# its2.net
KiCad netlist of a schematic drawn in EAGLE
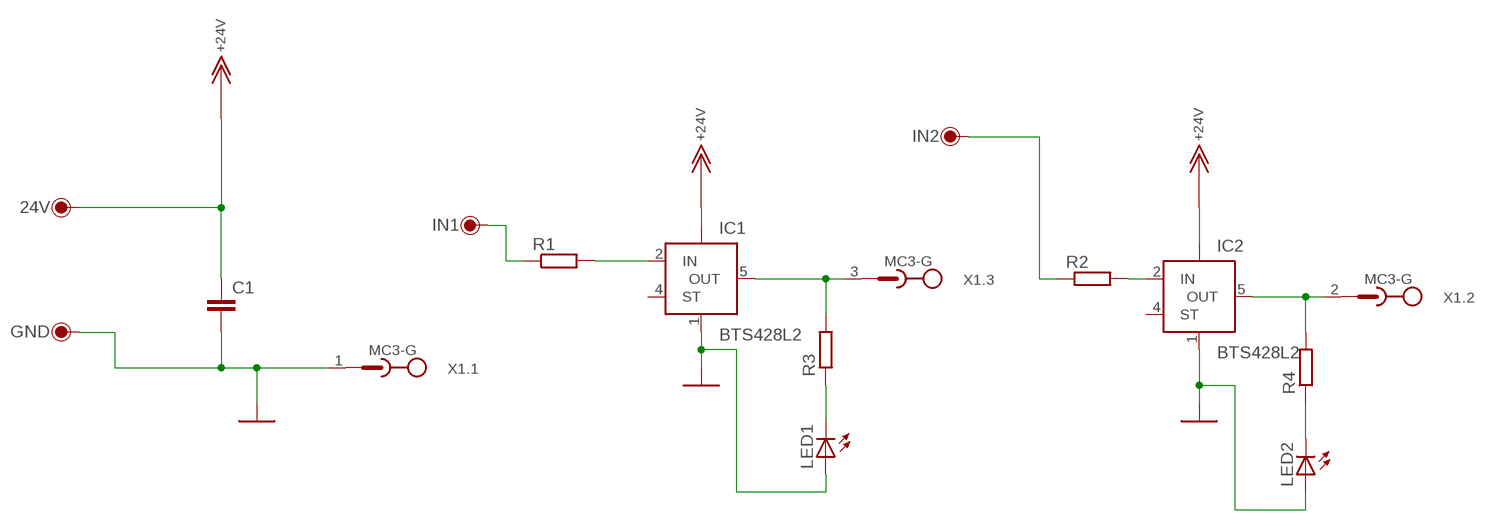
[diagram p0: schematic, sheet 1]

(export (version "E")
  (design (tool "Eeschema 10.0.6"))
  (components
    (comp (ref "24V")
      (value "PINGERAD")
      (footprint "eagle-import:PINGERAD")
      (libsource (lib "eagle-import") (part "PINGERAD"))
    )
    (comp (ref "C1")
      (value "C-EUC0805K")
      (footprint "eagle-import:C0805K")
      (libsource (lib "eagle-import") (part "C-EUC0805K"))
    )
    (comp (ref "GND")
      (value "PINGERAD")
      (footprint "eagle-import:PINGERAD")
      (libsource (lib "eagle-import") (part "PINGERAD"))
    )
    (comp (ref "IC1")
      (value "BTS428L2")
      (footprint "eagle-import:TO252-5-11")
      (libsource (lib "eagle-import") (part "BTS428L2"))
    )
    (comp (ref "IC2")
      (value "BTS428L2")
      (footprint "eagle-import:TO252-5-11")
      (libsource (lib "eagle-import") (part "BTS428L2"))
    )
    (comp (ref "IN1")
      (value "PINGERAD")
      (footprint "eagle-import:PINGERAD")
      (libsource (lib "eagle-import") (part "PINGERAD"))
    )
    (comp (ref "IN2")
      (value "PINGERAD")
      (footprint "eagle-import:PINGERAD")
      (libsource (lib "eagle-import") (part "PINGERAD"))
    )
    (comp (ref "LED1")
      (value "LEDSML1206")
      (footprint "eagle-import:SML1206")
      (libsource (lib "eagle-import") (part "LEDSML1206"))
    )
    (comp (ref "LED2")
      (value "LEDSML1206")
      (footprint "eagle-import:SML1206")
      (libsource (lib "eagle-import") (part "LEDSML1206"))
    )
    (comp (ref "R1")
      (value "R-EU_M0805")
      (footprint "eagle-import:M0805")
      (libsource (lib "eagle-import") (part "R-EU_M0805"))
    )
    (comp (ref "R2")
      (value "R-EU_M0805")
      (footprint "eagle-import:M0805")
      (libsource (lib "eagle-import") (part "R-EU_M0805"))
    )
    (comp (ref "R3")
      (value "R-EU_R0805")
      (footprint "eagle-import:R0805")
      (libsource (lib "eagle-import") (part "R-EU_R0805"))
    )
    (comp (ref "R4")
      (value "R-EU_R0805")
      (footprint "eagle-import:R0805")
      (libsource (lib "eagle-import") (part "R-EU_R0805"))
    )
    (comp (ref "X1")
      (value "MC3-G")
      (footprint "eagle-import:MC3-G")
      (libsource (lib "eagle-import") (part "MC3-G"))
    )
  )
  (nets
    (net (code "1") (name "+24V") (class "Default")
      (node (ref "24V") (pin "1") (pinfunction "1_1") (pintype "bidirectional"))
      (node (ref "C1") (pin "1") (pinfunction "1_1") (pintype "passive"))
      (node (ref "IC1") (pin "TAB") (pinfunction "VBB_TAB") (pintype "power_in"))
      (node (ref "IC2") (pin "TAB") (pinfunction "VBB_TAB") (pintype "power_in"))
    )
    (net (code "2") (name "GND") (class "Default")
      (node (ref "C1") (pin "2") (pinfunction "2_2") (pintype "passive"))
      (node (ref "GND") (pin "1") (pinfunction "1_1") (pintype "bidirectional"))
      (node (ref "IC1") (pin "1") (pinfunction "GND_1") (pintype "power_in"))
      (node (ref "IC2") (pin "1") (pinfunction "GND_1") (pintype "power_in"))
      (node (ref "LED1") (pin "A") (pinfunction "A_A") (pintype "passive"))
      (node (ref "LED2") (pin "A") (pinfunction "A_A") (pintype "passive"))
      (node (ref "X1") (pin "1") (pinfunction "SK_1") (pintype "passive"))
    )
    (net (code "3") (name "Net-(IC1-IN)") (class "Default")
      (node (ref "IC1") (pin "2") (pinfunction "IN_2") (pintype "input"))
      (node (ref "R1") (pin "2") (pinfunction "2_2") (pintype "passive"))
    )
    (net (code "4") (name "Net-(IC1-OUT)") (class "Default")
      (node (ref "IC1") (pin "5") (pinfunction "OUT_5") (pintype "output"))
      (node (ref "R3") (pin "2") (pinfunction "2_2") (pintype "passive"))
      (node (ref "X1") (pin "3") (pinfunction "SK_3") (pintype "passive"))
    )
    (net (code "5") (name "Net-(IC2-IN)") (class "Default")
      (node (ref "IC2") (pin "2") (pinfunction "IN_2") (pintype "input"))
      (node (ref "R2") (pin "2") (pinfunction "2_2") (pintype "passive"))
    )
    (net (code "6") (name "Net-(IC2-OUT)") (class "Default")
      (node (ref "IC2") (pin "5") (pinfunction "OUT_5") (pintype "output"))
      (node (ref "R4") (pin "2") (pinfunction "2_2") (pintype "passive"))
      (node (ref "X1") (pin "2") (pinfunction "SK_2") (pintype "passive"))
    )
    (net (code "7") (name "Net-(IN1-Pad1)") (class "Default")
      (node (ref "IN1") (pin "1") (pinfunction "1_1") (pintype "bidirectional"))
      (node (ref "R1") (pin "1") (pinfunction "1_1") (pintype "passive"))
    )
    (net (code "8") (name "Net-(IN2-Pad1)") (class "Default")
      (node (ref "IN2") (pin "1") (pinfunction "1_1") (pintype "bidirectional"))
      (node (ref "R2") (pin "1") (pinfunction "1_1") (pintype "passive"))
    )
    (net (code "9") (name "Net-(LED1-PadC)") (class "Default")
      (node (ref "LED1") (pin "C") (pinfunction "C_C") (pintype "passive"))
      (node (ref "R3") (pin "1") (pinfunction "1_1") (pintype "passive"))
    )
    (net (code "10") (name "Net-(LED2-PadC)") (class "Default")
      (node (ref "LED2") (pin "C") (pinfunction "C_C") (pintype "passive"))
      (node (ref "R4") (pin "1") (pinfunction "1_1") (pintype "passive"))
    )
    (net (code "11") (name "unconnected-(IC1-ST-Pad4)") (class "Default")
      (node (ref "IC1") (pin "4") (pinfunction "ST_4") (pintype "input"))
    )
    (net (code "12") (name "unconnected-(IC2-ST-Pad4)") (class "Default")
      (node (ref "IC2") (pin "4") (pinfunction "ST_4") (pintype "input"))
    )
  )
)
